# generic-switch-board.net
KiCad netlist of a schematic drawn in EAGLE
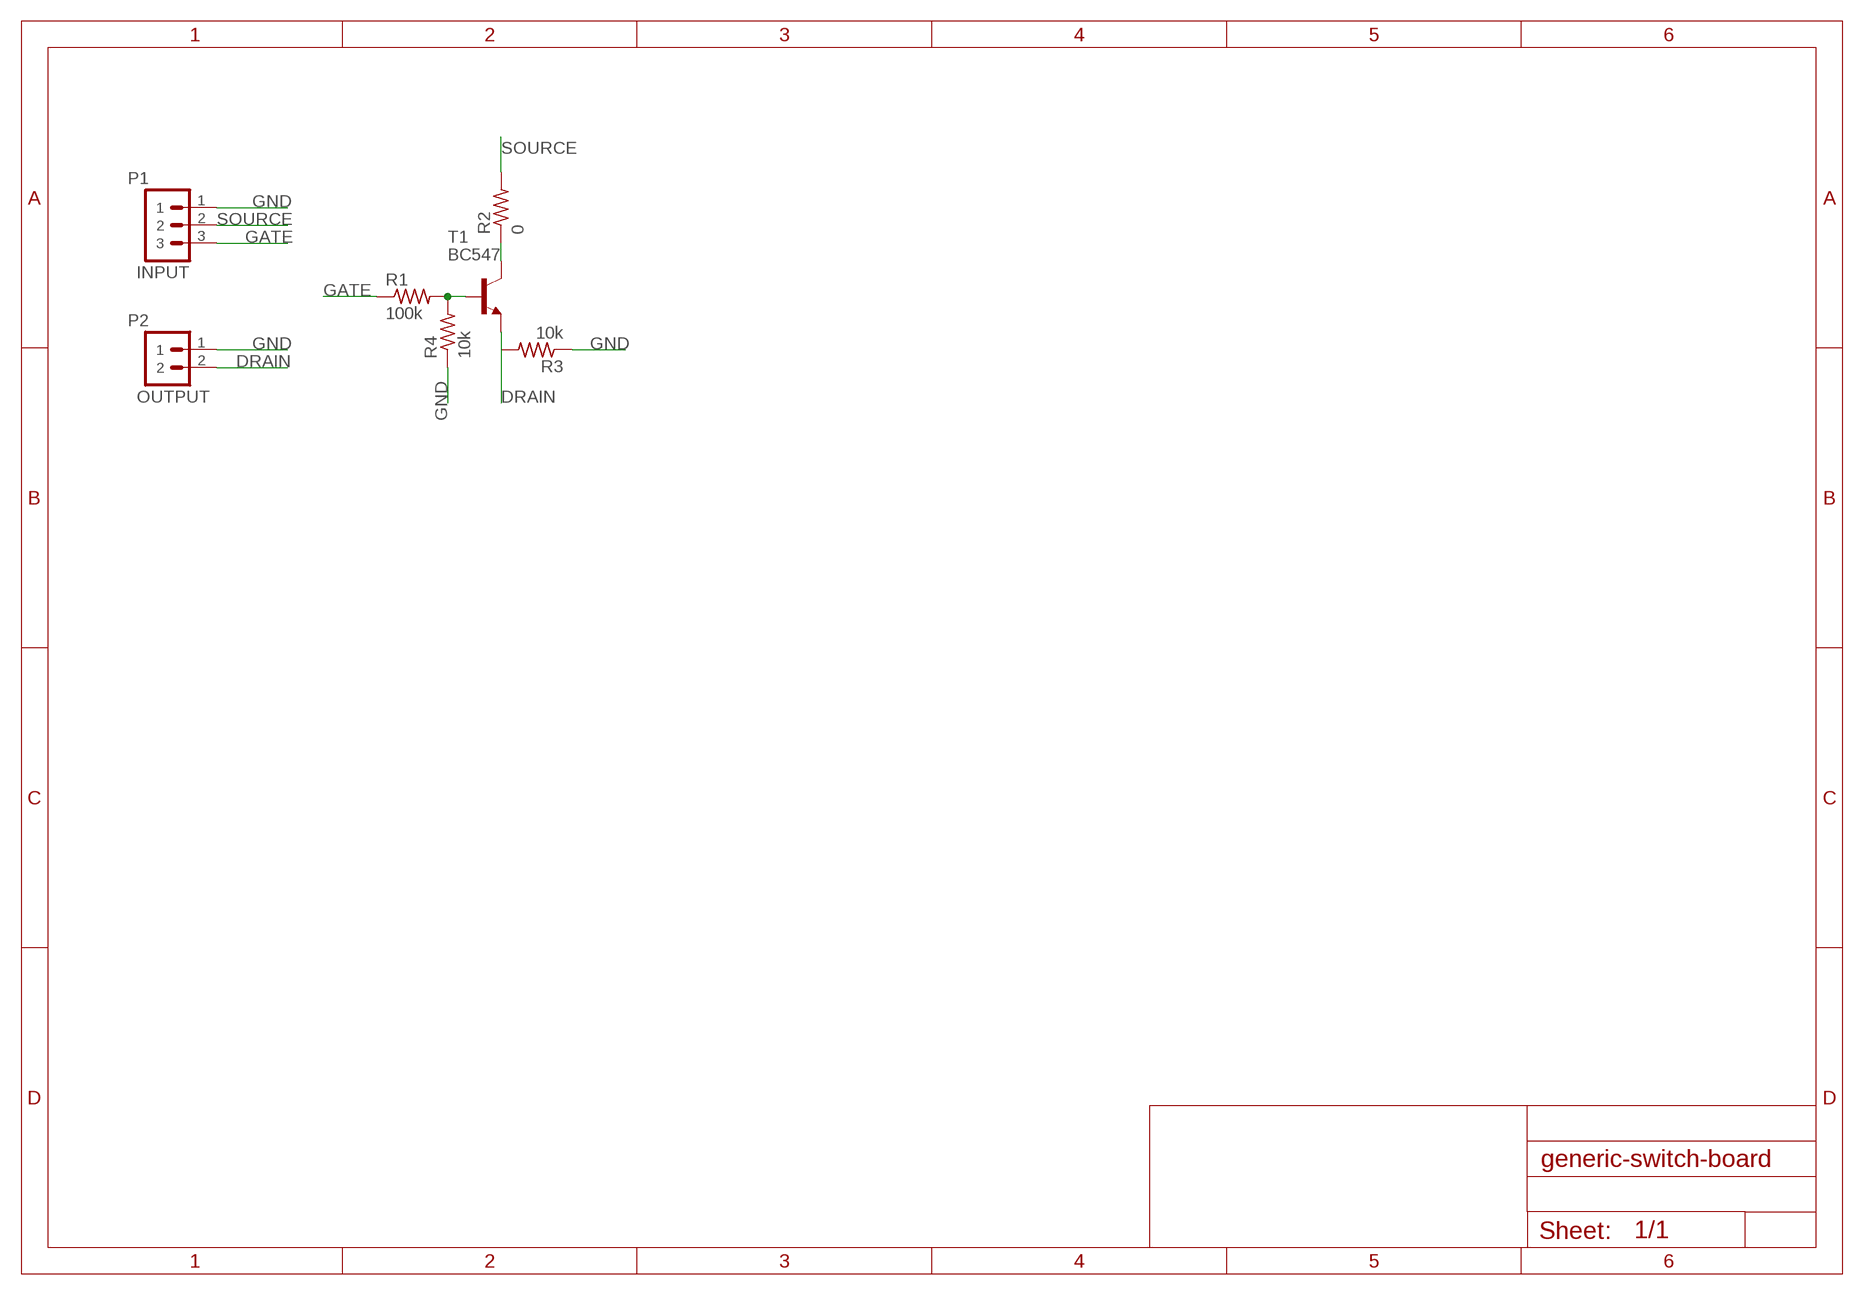
[diagram p0: schematic, sheet 1]

(export (version "E")
  (design (tool "Eeschema 10.0.6"))
  (components
    (comp (ref "P1")
      (value "IN")
      (footprint "eagle-import:PIN-HEADER-3PIN")
      (libsource (lib "eagle-import") (part "PIN-HEADER-3PIN"))
    )
    (comp (ref "P2")
      (value "OUT")
      (footprint "eagle-import:PIN-HEADER-2PIN")
      (libsource (lib "eagle-import") (part "PIN-HEADER-2PIN"))
    )
    (comp (ref "R1")
      (value "100k")
      (footprint "eagle-import:RESISTOR-V3")
      (libsource (lib "eagle-import") (part "RESISTORV3"))
    )
    (comp (ref "R2")
      (value "0")
      (footprint "eagle-import:RESISTOR-V2")
      (libsource (lib "eagle-import") (part "RESISTORV2"))
    )
    (comp (ref "R3")
      (value "10k")
      (footprint "eagle-import:RESISTOR-V1")
      (libsource (lib "eagle-import") (part "RESISTORV1"))
    )
    (comp (ref "R4")
      (value "10k")
      (footprint "eagle-import:RESISTOR-V1")
      (libsource (lib "eagle-import") (part "RESISTORV1"))
    )
    (comp (ref "T1")
      (value "BC547")
      (footprint "eagle-import:TO-92-FLAT")
      (libsource (lib "eagle-import") (part "2N3904"))
    )
  )
  (nets
    (net (code "1") (name "/DRAIN") (class "Default")
      (node (ref "P2") (pin "2") (pinfunction "2_2") (pintype "passive"))
      (node (ref "R3") (pin "2") (pinfunction "2_2") (pintype "passive"))
      (node (ref "T1") (pin "1") (pinfunction "E_1") (pintype "passive"))
    )
    (net (code "2") (name "/GATE") (class "Default")
      (node (ref "P1") (pin "3") (pinfunction "3_3") (pintype "passive"))
      (node (ref "R1") (pin "1") (pinfunction "1_1") (pintype "passive"))
    )
    (net (code "3") (name "/GND") (class "Default")
      (node (ref "P1") (pin "1") (pinfunction "1_1") (pintype "passive"))
      (node (ref "P2") (pin "1") (pinfunction "1_1") (pintype "passive"))
      (node (ref "R3") (pin "1") (pinfunction "1_1") (pintype "passive"))
      (node (ref "R4") (pin "1") (pinfunction "1_1") (pintype "passive"))
    )
    (net (code "4") (name "/SOURCE") (class "Default")
      (node (ref "P1") (pin "2") (pinfunction "2_2") (pintype "passive"))
      (node (ref "R2") (pin "2") (pinfunction "2_2") (pintype "passive"))
    )
    (net (code "5") (name "Net-(T1-B)") (class "Default")
      (node (ref "R1") (pin "2") (pinfunction "2_2") (pintype "passive"))
      (node (ref "R4") (pin "2") (pinfunction "2_2") (pintype "passive"))
      (node (ref "T1") (pin "2") (pinfunction "B_2") (pintype "passive"))
    )
    (net (code "6") (name "Net-(T1-C)") (class "Default")
      (node (ref "R2") (pin "1") (pinfunction "1_1") (pintype "passive"))
      (node (ref "T1") (pin "3") (pinfunction "C_3") (pintype "passive"))
    )
  )
)
